# Nusbio_Flash_Extension.net
KiCad netlist of a schematic drawn in EAGLE
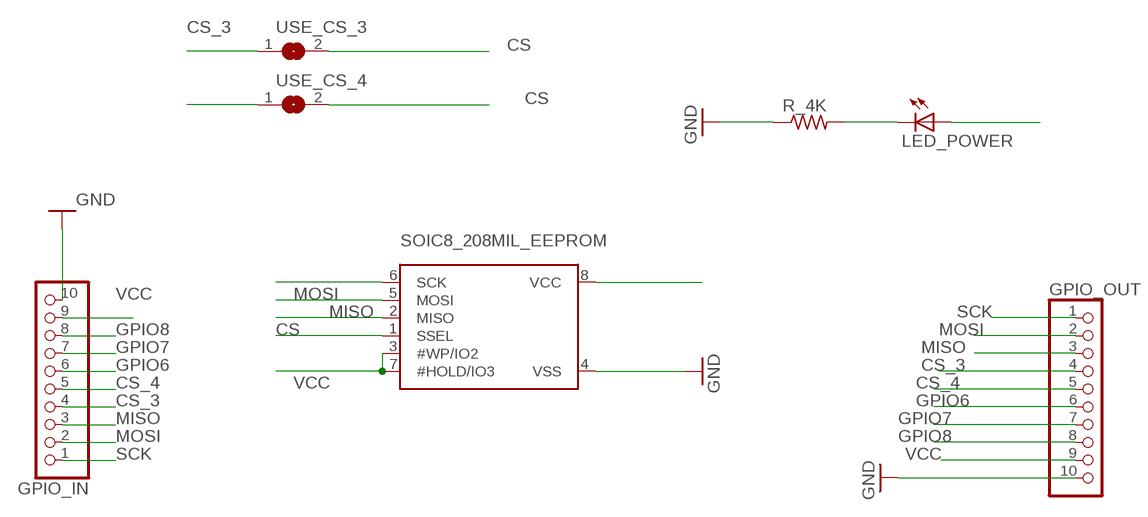
[diagram p0: schematic, sheet 1]

(export (version "E")
  (design (tool "Eeschema 10.0.6"))
  (components
    (comp (ref "GPIO_IN")
      (value "PINHD-1X10")
      (footprint "eagle-import:1X10-BIG")
      (libsource (lib "eagle-import") (part "PINHD-1X10"))
    )
    (comp (ref "GPIO_OUT")
      (value "PINHD-1X10")
      (footprint "eagle-import:1X10-BIG")
      (libsource (lib "eagle-import") (part "PINHD-1X10"))
    )
    (comp (ref "LED_POWER")
      (value "LEDSMT1206")
      (footprint "eagle-import:1206")
      (libsource (lib "eagle-import") (part "LEDSMT1206"))
    )
    (comp (ref "R_4K")
      (value "R-US_R1206")
      (footprint "eagle-import:R1206")
      (libsource (lib "eagle-import") (part "R-US_R1206"))
    )
    (comp (ref "SOIC8_208MIL_EEPROM")
      (value "SPIFLASH_SOIC8208MIL")
      (footprint "eagle-import:SOIC8_208MIL")
      (libsource (lib "eagle-import") (part "SPIFLASH_SOIC8208MIL"))
    )
    (comp (ref "USE_CS_3")
      (value "SOLDERJUMPERREFLOW")
      (footprint "eagle-import:SOLDERJUMPER_REFLOW")
      (libsource (lib "eagle-import") (part "SOLDERJUMPERREFLOW"))
    )
    (comp (ref "USE_CS_4")
      (value "SOLDERJUMPERREFLOW")
      (footprint "eagle-import:SOLDERJUMPER_REFLOW")
      (libsource (lib "eagle-import") (part "SOLDERJUMPERREFLOW"))
    )
  )
  (nets
    (net (code "1") (name "/CS") (class "Default")
      (node (ref "SOIC8_208MIL_EEPROM") (pin "1") (pinfunction "SSEL_1") (pintype "bidirectional"))
      (node (ref "USE_CS_3") (pin "2") (pinfunction "2_2") (pintype "passive"))
      (node (ref "USE_CS_4") (pin "2") (pinfunction "2_2") (pintype "passive"))
    )
    (net (code "2") (name "/CS_3") (class "Default")
      (node (ref "GPIO_IN") (pin "4") (pinfunction "4_4") (pintype "passive"))
      (node (ref "GPIO_OUT") (pin "4") (pinfunction "4_4") (pintype "passive"))
      (node (ref "USE_CS_3") (pin "1") (pinfunction "1_1") (pintype "passive"))
    )
    (net (code "3") (name "/CS_4") (class "Default")
      (node (ref "GPIO_IN") (pin "5") (pinfunction "5_5") (pintype "passive"))
      (node (ref "GPIO_OUT") (pin "5") (pinfunction "5_5") (pintype "passive"))
      (node (ref "USE_CS_4") (pin "1") (pinfunction "1_1") (pintype "passive"))
    )
    (net (code "4") (name "/GPIO6") (class "Default")
      (node (ref "GPIO_IN") (pin "6") (pinfunction "6_6") (pintype "passive"))
      (node (ref "GPIO_OUT") (pin "6") (pinfunction "6_6") (pintype "passive"))
    )
    (net (code "5") (name "/GPIO7") (class "Default")
      (node (ref "GPIO_IN") (pin "7") (pinfunction "7_7") (pintype "passive"))
      (node (ref "GPIO_OUT") (pin "7") (pinfunction "7_7") (pintype "passive"))
    )
    (net (code "6") (name "/GPIO8") (class "Default")
      (node (ref "GPIO_IN") (pin "8") (pinfunction "8_8") (pintype "passive"))
      (node (ref "GPIO_OUT") (pin "8") (pinfunction "8_8") (pintype "passive"))
    )
    (net (code "7") (name "/MISO") (class "Default")
      (node (ref "GPIO_IN") (pin "3") (pinfunction "3_3") (pintype "passive"))
      (node (ref "GPIO_OUT") (pin "3") (pinfunction "3_3") (pintype "passive"))
      (node (ref "SOIC8_208MIL_EEPROM") (pin "2") (pinfunction "MISO_2") (pintype "bidirectional"))
    )
    (net (code "8") (name "/MOSI") (class "Default")
      (node (ref "GPIO_IN") (pin "2") (pinfunction "2_2") (pintype "passive"))
      (node (ref "GPIO_OUT") (pin "2") (pinfunction "2_2") (pintype "passive"))
      (node (ref "SOIC8_208MIL_EEPROM") (pin "5") (pinfunction "MOSI_5") (pintype "bidirectional"))
    )
    (net (code "9") (name "/SCK") (class "Default")
      (node (ref "GPIO_IN") (pin "1") (pinfunction "1_1") (pintype "passive"))
      (node (ref "GPIO_OUT") (pin "1") (pinfunction "1_1") (pintype "passive"))
      (node (ref "SOIC8_208MIL_EEPROM") (pin "6") (pinfunction "SCK_6") (pintype "bidirectional"))
    )
    (net (code "10") (name "/VCC") (class "Default")
      (node (ref "GPIO_IN") (pin "9") (pinfunction "9_9") (pintype "passive"))
      (node (ref "GPIO_OUT") (pin "9") (pinfunction "9_9") (pintype "passive"))
      (node (ref "LED_POWER") (pin "A") (pinfunction "A_A") (pintype "passive"))
      (node (ref "SOIC8_208MIL_EEPROM") (pin "3") (pinfunction "#WP/IO2_3") (pintype "bidirectional"))
      (node (ref "SOIC8_208MIL_EEPROM") (pin "7") (pinfunction "#HOLD/IO3_7") (pintype "bidirectional"))
      (node (ref "SOIC8_208MIL_EEPROM") (pin "8") (pinfunction "VCC_8") (pintype "bidirectional"))
    )
    (net (code "11") (name "GND") (class "Default")
      (node (ref "GPIO_IN") (pin "10") (pinfunction "10_10") (pintype "passive"))
      (node (ref "GPIO_OUT") (pin "10") (pinfunction "10_10") (pintype "passive"))
      (node (ref "R_4K") (pin "1") (pinfunction "1_1") (pintype "passive"))
      (node (ref "SOIC8_208MIL_EEPROM") (pin "4") (pinfunction "VSS_4") (pintype "bidirectional"))
    )
    (net (code "12") (name "Net-(LED_POWER-PadC)") (class "Default")
      (node (ref "LED_POWER") (pin "C") (pinfunction "C_C") (pintype "passive"))
      (node (ref "R_4K") (pin "2") (pinfunction "2_2") (pintype "passive"))
    )
  )
)
